# Motherboard_simple.net
KiCad netlist of a schematic drawn in EAGLE
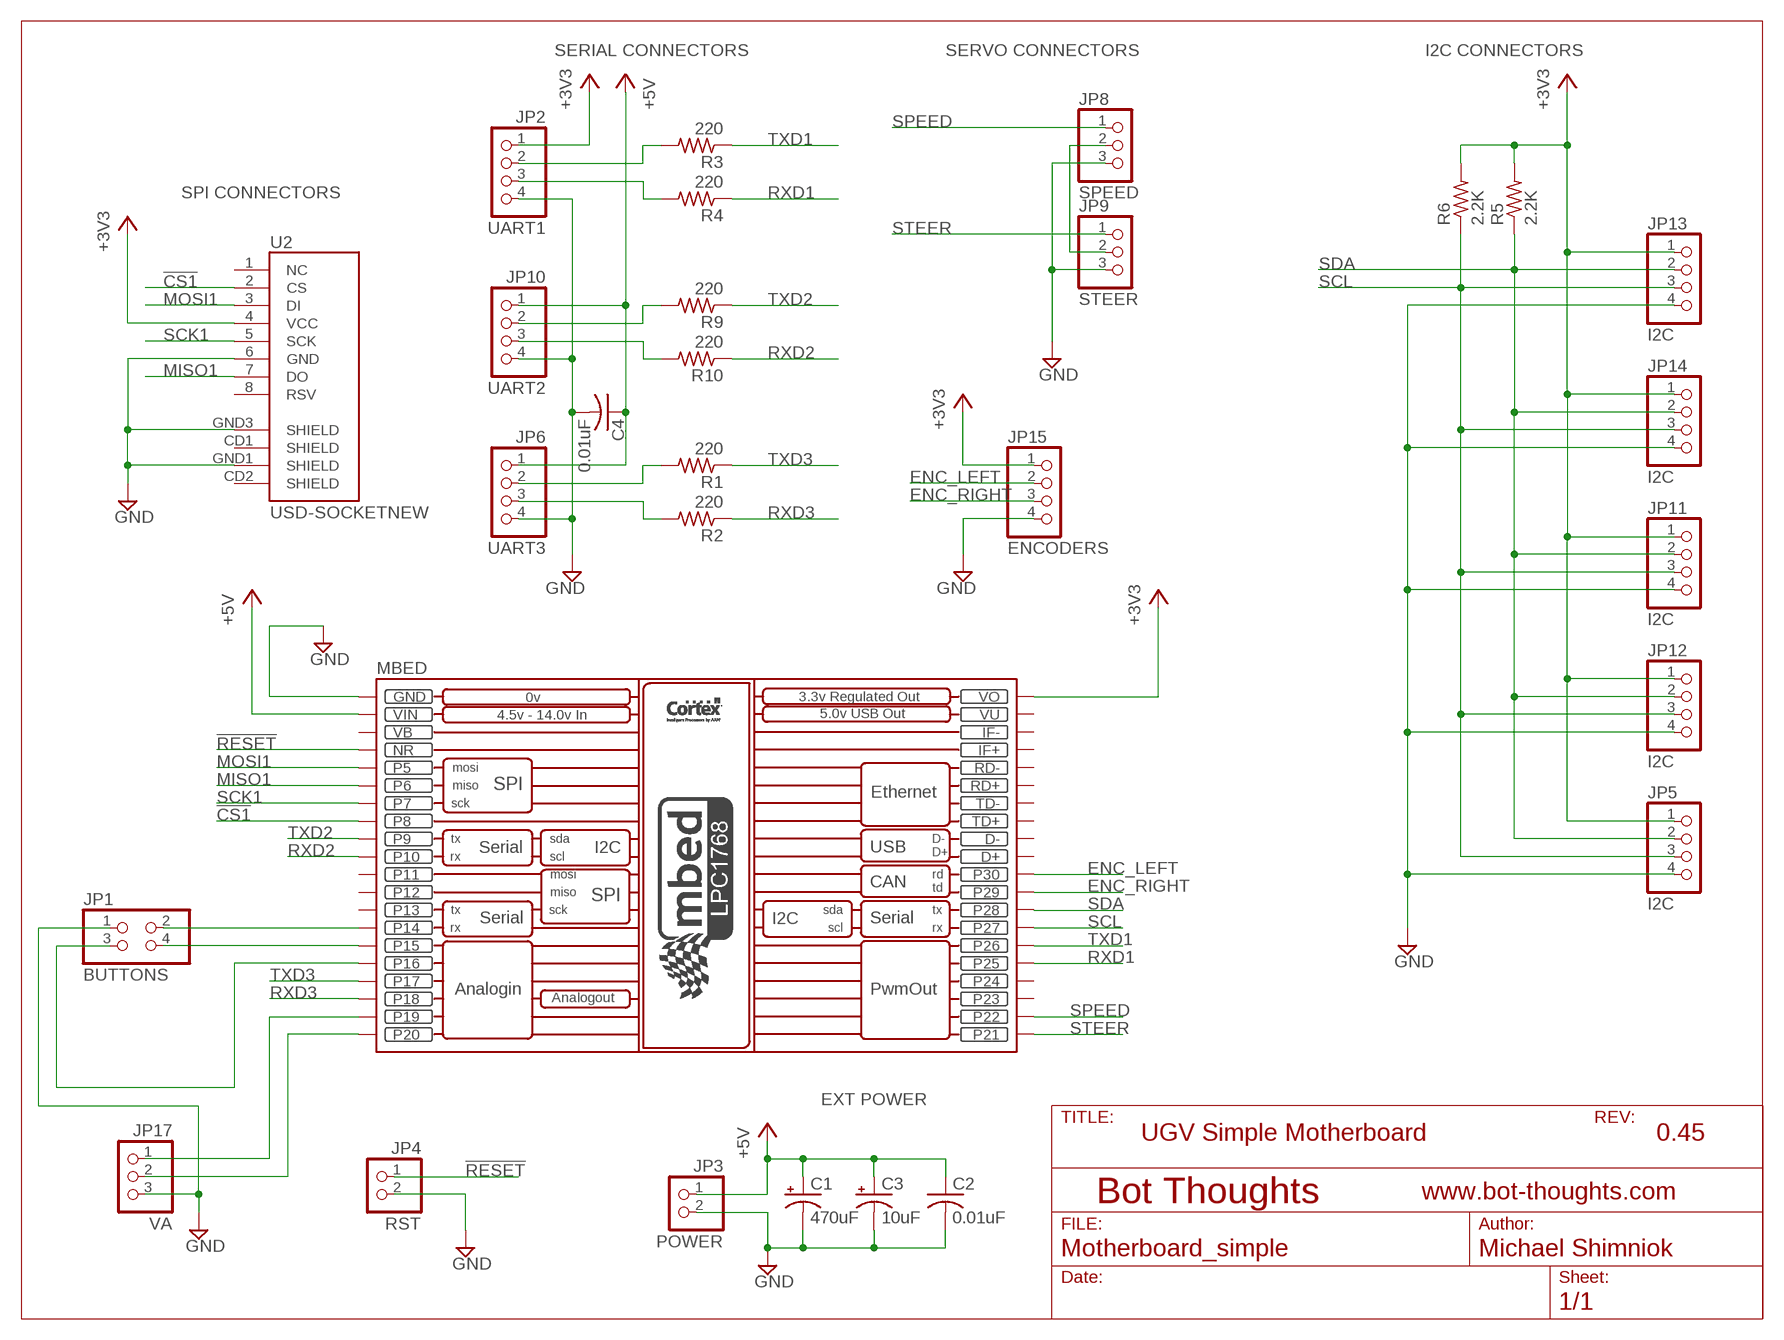
[diagram p0: schematic, sheet 1]

(export (version "E")
  (design (tool "Eeschema 10.0.6"))
  (components
    (comp (ref "C1")
      (value "470uF")
      (footprint "eagle-import:E2,5-6")
      (libsource (lib "eagle-import") (part "CPOL-USE2.5-6"))
    )
    (comp (ref "C2")
      (value "0.01uF")
      (footprint "eagle-import:C050-025X075")
      (libsource (lib "eagle-import") (part "C-US050-025X075"))
    )
    (comp (ref "C3")
      (value "10uF")
      (footprint "eagle-import:E2,5-6")
      (libsource (lib "eagle-import") (part "CPOL-USE2.5-6"))
    )
    (comp (ref "C4")
      (value "0.01uF")
      (footprint "eagle-import:C050-025X075")
      (libsource (lib "eagle-import") (part "C-US050-025X075"))
    )
    (comp (ref "JP1")
      (value "BUTTONS")
      (footprint "eagle-import:2X02")
      (libsource (lib "eagle-import") (part "PINHD-2X02_2.54"))
    )
    (comp (ref "JP2")
      (value "UART1")
      (footprint "eagle-import:1X04-S")
      (libsource (lib "eagle-import") (part "PINHD-1X04_2.54-S"))
    )
    (comp (ref "JP3")
      (value "POWER")
      (footprint "eagle-import:1X02-S")
      (libsource (lib "eagle-import") (part "PINHD-1X02_2.54-S"))
    )
    (comp (ref "JP4")
      (value "RST")
      (footprint "eagle-import:1X02-S")
      (libsource (lib "eagle-import") (part "PINHD-1X02_2.54-S"))
    )
    (comp (ref "JP5")
      (value "I2C")
      (footprint "eagle-import:1X04-S")
      (libsource (lib "eagle-import") (part "PINHD-1X04_2.54-S"))
    )
    (comp (ref "JP6")
      (value "UART3")
      (footprint "eagle-import:1X04-S")
      (libsource (lib "eagle-import") (part "PINHD-1X04_2.54-S"))
    )
    (comp (ref "JP8")
      (value "SPEED")
      (footprint "eagle-import:1X03-S")
      (libsource (lib "eagle-import") (part "PINHD-1X03_2.54-S"))
    )
    (comp (ref "JP9")
      (value "STEER")
      (footprint "eagle-import:1X03-S")
      (libsource (lib "eagle-import") (part "PINHD-1X03_2.54-S"))
    )
    (comp (ref "JP10")
      (value "UART2")
      (footprint "eagle-import:1X04-S")
      (libsource (lib "eagle-import") (part "PINHD-1X04_2.54-S"))
    )
    (comp (ref "JP11")
      (value "I2C")
      (footprint "eagle-import:1X04-S")
      (libsource (lib "eagle-import") (part "PINHD-1X04_2.54-S"))
    )
    (comp (ref "JP12")
      (value "I2C")
      (footprint "eagle-import:1X04-S")
      (libsource (lib "eagle-import") (part "PINHD-1X04_2.54-S"))
    )
    (comp (ref "JP13")
      (value "I2C")
      (footprint "eagle-import:1X04-S")
      (libsource (lib "eagle-import") (part "PINHD-1X04_2.54-S"))
    )
    (comp (ref "JP14")
      (value "I2C")
      (footprint "eagle-import:1X04-S")
      (libsource (lib "eagle-import") (part "PINHD-1X04_2.54-S"))
    )
    (comp (ref "JP15")
      (value "ENCODERS")
      (footprint "eagle-import:1X04-S")
      (libsource (lib "eagle-import") (part "PINHD-1X04_2.54-S"))
    )
    (comp (ref "JP17")
      (value "VA")
      (footprint "eagle-import:1X03-S")
      (libsource (lib "eagle-import") (part "PINHD-1X03_2.54-S"))
    )
    (comp (ref "MBED")
      (value "MBED_NXP_LPC1768")
      (footprint "eagle-import:MBED-KIT")
      (fields (field (name "MPN") "2212S-20SG-85"))
      (libsource (lib "eagle-import") (part "MBED_NXP_LPC1768"))
    )
    (comp (ref "R1")
      (value "220")
      (footprint "eagle-import:0204_5")
      (fields (field (name "MPN") "WCR0805-220RFI"))
      (libsource (lib "eagle-import") (part "R-US_0204/5"))
    )
    (comp (ref "R2")
      (value "220")
      (footprint "eagle-import:0204_5")
      (fields (field (name "MPN") "WCR0805-220RFI"))
      (libsource (lib "eagle-import") (part "R-US_0204/5"))
    )
    (comp (ref "R3")
      (value "220")
      (footprint "eagle-import:0204_5")
      (fields (field (name "MPN") "WCR0805-220RFI"))
      (libsource (lib "eagle-import") (part "R-US_0204/5"))
    )
    (comp (ref "R4")
      (value "220")
      (footprint "eagle-import:0204_5")
      (fields (field (name "MPN") "WCR0805-220RFI"))
      (libsource (lib "eagle-import") (part "R-US_0204/5"))
    )
    (comp (ref "R5")
      (value "2.2K")
      (footprint "eagle-import:0204_5")
      (libsource (lib "eagle-import") (part "R-US_0204/5"))
    )
    (comp (ref "R6")
      (value "2.2K")
      (footprint "eagle-import:0204_5")
      (libsource (lib "eagle-import") (part "R-US_0204/5"))
    )
    (comp (ref "R9")
      (value "220")
      (footprint "eagle-import:0204_5")
      (fields (field (name "MPN") "WCR0805-220RFI"))
      (libsource (lib "eagle-import") (part "R-US_0204/5"))
    )
    (comp (ref "R10")
      (value "220")
      (footprint "eagle-import:0204_5")
      (fields (field (name "MPN") "WCR0805-220RFI"))
      (libsource (lib "eagle-import") (part "R-US_0204/5"))
    )
    (comp (ref "U2")
      (value "USD-SOCKETNEW")
      (footprint "eagle-import:MICRO-SD-SOCKET-PP")
      (libsource (lib "eagle-import") (part "USD-SOCKETNEW"))
    )
  )
  (nets
    (net (code "1") (name "+3V3") (class "Default")
      (node (ref "JP11") (pin "1") (pinfunction "1_1") (pintype "passive"))
      (node (ref "JP12") (pin "1") (pinfunction "1_1") (pintype "passive"))
      (node (ref "JP13") (pin "1") (pinfunction "1_1") (pintype "passive"))
      (node (ref "JP14") (pin "1") (pinfunction "1_1") (pintype "passive"))
      (node (ref "JP15") (pin "1") (pinfunction "1_1") (pintype "passive"))
      (node (ref "JP2") (pin "1") (pinfunction "1_1") (pintype "passive"))
      (node (ref "JP5") (pin "1") (pinfunction "1_1") (pintype "passive"))
      (node (ref "MBED") (pin "VOUT") (pinfunction "VO_VOUT") (pintype "power_in"))
      (node (ref "R5") (pin "2") (pinfunction "2_2") (pintype "passive"))
      (node (ref "R6") (pin "2") (pinfunction "2_2") (pintype "passive"))
      (node (ref "U2") (pin "4") (pinfunction "VCC_4") (pintype "bidirectional"))
    )
    (net (code "2") (name "+5V") (class "Default")
      (node (ref "C1") (pin "+") (pinfunction "+_+") (pintype "passive"))
      (node (ref "C2") (pin "1") (pinfunction "1_1") (pintype "passive"))
      (node (ref "C3") (pin "+") (pinfunction "+_+") (pintype "passive"))
      (node (ref "C4") (pin "1") (pinfunction "1_1") (pintype "passive"))
      (node (ref "JP10") (pin "1") (pinfunction "1_1") (pintype "passive"))
      (node (ref "JP3") (pin "1") (pinfunction "1_1") (pintype "passive"))
      (node (ref "JP6") (pin "1") (pinfunction "1_1") (pintype "passive"))
      (node (ref "MBED") (pin "VIN") (pinfunction "VIN_VIN") (pintype "power_in"))
    )
    (net (code "3") (name "/ENC_LEFT") (class "Default")
      (node (ref "JP15") (pin "2") (pinfunction "2_2") (pintype "passive"))
      (node (ref "MBED") (pin "P$30") (pinfunction "P30_P$30") (pintype "bidirectional"))
    )
    (net (code "4") (name "/ENC_RIGHT") (class "Default")
      (node (ref "JP15") (pin "3") (pinfunction "3_3") (pintype "passive"))
      (node (ref "MBED") (pin "P$29") (pinfunction "P29_P$29") (pintype "bidirectional"))
    )
    (net (code "5") (name "/MISO1") (class "Default")
      (node (ref "MBED") (pin "P$6") (pinfunction "P6_P$6") (pintype "bidirectional"))
      (node (ref "U2") (pin "7") (pinfunction "DO_7") (pintype "bidirectional"))
    )
    (net (code "6") (name "/MOSI1") (class "Default")
      (node (ref "MBED") (pin "P$5") (pinfunction "P5_P$5") (pintype "bidirectional"))
      (node (ref "U2") (pin "3") (pinfunction "DI_3") (pintype "bidirectional"))
    )
    (net (code "7") (name "/RXD1") (class "Default")
      (node (ref "MBED") (pin "P$25") (pinfunction "P25_P$25") (pintype "bidirectional"))
      (node (ref "R4") (pin "1") (pinfunction "1_1") (pintype "passive"))
    )
    (net (code "8") (name "/RXD2") (class "Default")
      (node (ref "MBED") (pin "P$10") (pinfunction "P10_P$10") (pintype "bidirectional"))
      (node (ref "R10") (pin "1") (pinfunction "1_1") (pintype "passive"))
    )
    (net (code "9") (name "/RXD3") (class "Default")
      (node (ref "MBED") (pin "P$18") (pinfunction "P18_P$18") (pintype "bidirectional"))
      (node (ref "R2") (pin "1") (pinfunction "1_1") (pintype "passive"))
    )
    (net (code "10") (name "/SCK1") (class "Default")
      (node (ref "MBED") (pin "P$7") (pinfunction "P7_P$7") (pintype "bidirectional"))
      (node (ref "U2") (pin "5") (pinfunction "SCK_5") (pintype "bidirectional"))
    )
    (net (code "11") (name "/SCL") (class "Default")
      (node (ref "JP11") (pin "3") (pinfunction "3_3") (pintype "passive"))
      (node (ref "JP12") (pin "3") (pinfunction "3_3") (pintype "passive"))
      (node (ref "JP13") (pin "3") (pinfunction "3_3") (pintype "passive"))
      (node (ref "JP14") (pin "3") (pinfunction "3_3") (pintype "passive"))
      (node (ref "JP5") (pin "3") (pinfunction "3_3") (pintype "passive"))
      (node (ref "MBED") (pin "P$27") (pinfunction "P27_P$27") (pintype "bidirectional"))
      (node (ref "R6") (pin "1") (pinfunction "1_1") (pintype "passive"))
    )
    (net (code "12") (name "/SDA") (class "Default")
      (node (ref "JP11") (pin "2") (pinfunction "2_2") (pintype "passive"))
      (node (ref "JP12") (pin "2") (pinfunction "2_2") (pintype "passive"))
      (node (ref "JP13") (pin "2") (pinfunction "2_2") (pintype "passive"))
      (node (ref "JP14") (pin "2") (pinfunction "2_2") (pintype "passive"))
      (node (ref "JP5") (pin "2") (pinfunction "2_2") (pintype "passive"))
      (node (ref "MBED") (pin "P$28") (pinfunction "P28_P$28") (pintype "bidirectional"))
      (node (ref "R5") (pin "1") (pinfunction "1_1") (pintype "passive"))
    )
    (net (code "13") (name "/SPEED") (class "Default")
      (node (ref "JP8") (pin "1") (pinfunction "1_1") (pintype "passive"))
      (node (ref "MBED") (pin "P$22") (pinfunction "P22_P$22") (pintype "bidirectional"))
    )
    (net (code "14") (name "/STEER") (class "Default")
      (node (ref "JP9") (pin "1") (pinfunction "1_1") (pintype "passive"))
      (node (ref "MBED") (pin "P$21") (pinfunction "P21_P$21") (pintype "bidirectional"))
    )
    (net (code "15") (name "/TXD1") (class "Default")
      (node (ref "MBED") (pin "P$26") (pinfunction "P26_P$26") (pintype "bidirectional"))
      (node (ref "R3") (pin "1") (pinfunction "1_1") (pintype "passive"))
    )
    (net (code "16") (name "/TXD2") (class "Default")
      (node (ref "MBED") (pin "P$9") (pinfunction "P9_P$9") (pintype "bidirectional"))
      (node (ref "R9") (pin "1") (pinfunction "1_1") (pintype "passive"))
    )
    (net (code "17") (name "/TXD3") (class "Default")
      (node (ref "MBED") (pin "P$17") (pinfunction "P17_P$17") (pintype "bidirectional"))
      (node (ref "R1") (pin "1") (pinfunction "1_1") (pintype "passive"))
    )
    (net (code "18") (name "/VB") (class "Default")
      (node (ref "MBED") (pin "VB") (pinfunction "VB_VB") (pintype "power_in"))
    )
    (net (code "19") (name "/VU") (class "Default")
      (node (ref "MBED") (pin "VU") (pinfunction "VU_VU") (pintype "power_in"))
    )
    (net (code "20") (name "/~{CS1}") (class "Default")
      (node (ref "MBED") (pin "P$8") (pinfunction "P8_P$8") (pintype "bidirectional"))
      (node (ref "U2") (pin "2") (pinfunction "CS_2") (pintype "bidirectional"))
    )
    (net (code "21") (name "/~{RESET}") (class "Default")
      (node (ref "JP4") (pin "1") (pinfunction "1_1") (pintype "passive"))
      (node (ref "MBED") (pin "NR") (pinfunction "NR_NR") (pintype "power_in"))
    )
    (net (code "22") (name "GND") (class "Default")
      (node (ref "C1") (pin "-") (pinfunction "-_-") (pintype "passive"))
      (node (ref "C2") (pin "2") (pinfunction "2_2") (pintype "passive"))
      (node (ref "C3") (pin "-") (pinfunction "-_-") (pintype "passive"))
      (node (ref "C4") (pin "2") (pinfunction "2_2") (pintype "passive"))
      (node (ref "JP1") (pin "1") (pinfunction "1_1") (pintype "passive"))
      (node (ref "JP10") (pin "4") (pinfunction "4_4") (pintype "passive"))
      (node (ref "JP11") (pin "4") (pinfunction "4_4") (pintype "passive"))
      (node (ref "JP12") (pin "4") (pinfunction "4_4") (pintype "passive"))
      (node (ref "JP13") (pin "4") (pinfunction "4_4") (pintype "passive"))
      (node (ref "JP14") (pin "4") (pinfunction "4_4") (pintype "passive"))
      (node (ref "JP15") (pin "4") (pinfunction "4_4") (pintype "passive"))
      (node (ref "JP17") (pin "3") (pinfunction "3_3") (pintype "passive"))
      (node (ref "JP2") (pin "4") (pinfunction "4_4") (pintype "passive"))
      (node (ref "JP3") (pin "2") (pinfunction "2_2") (pintype "passive"))
      (node (ref "JP4") (pin "2") (pinfunction "2_2") (pintype "passive"))
      (node (ref "JP5") (pin "4") (pinfunction "4_4") (pintype "passive"))
      (node (ref "JP6") (pin "4") (pinfunction "4_4") (pintype "passive"))
      (node (ref "JP8") (pin "3") (pinfunction "3_3") (pintype "passive"))
      (node (ref "JP9") (pin "3") (pinfunction "3_3") (pintype "passive"))
      (node (ref "MBED") (pin "GND") (pinfunction "GND_GND") (pintype "power_in"))
      (node (ref "U2") (pin "6") (pinfunction "GND_6") (pintype "bidirectional"))
      (node (ref "U2") (pin "GND1") (pinfunction "SHIELD_GND1") (pintype "bidirectional"))
      (node (ref "U2") (pin "GND3") (pinfunction "SHIELD_GND3") (pintype "bidirectional"))
    )
    (net (code "23") (name "Net-(JP2-Pad2)") (class "Default")
      (node (ref "JP2") (pin "2") (pinfunction "2_2") (pintype "passive"))
      (node (ref "R3") (pin "2") (pinfunction "2_2") (pintype "passive"))
    )
    (net (code "24") (name "Net-(JP2-Pad3)") (class "Default")
      (node (ref "JP2") (pin "3") (pinfunction "3_3") (pintype "passive"))
      (node (ref "R4") (pin "2") (pinfunction "2_2") (pintype "passive"))
    )
    (net (code "25") (name "Net-(JP6-Pad2)") (class "Default")
      (node (ref "JP6") (pin "2") (pinfunction "2_2") (pintype "passive"))
      (node (ref "R1") (pin "2") (pinfunction "2_2") (pintype "passive"))
    )
    (net (code "26") (name "Net-(JP6-Pad3)") (class "Default")
      (node (ref "JP6") (pin "3") (pinfunction "3_3") (pintype "passive"))
      (node (ref "R2") (pin "2") (pinfunction "2_2") (pintype "passive"))
    )
    (net (code "27") (name "Net-(JP8-Pad2)") (class "Default")
      (node (ref "JP8") (pin "2") (pinfunction "2_2") (pintype "passive"))
      (node (ref "JP9") (pin "2") (pinfunction "2_2") (pintype "passive"))
    )
    (net (code "28") (name "Net-(JP10-Pad2)") (class "Default")
      (node (ref "JP10") (pin "2") (pinfunction "2_2") (pintype "passive"))
      (node (ref "R9") (pin "2") (pinfunction "2_2") (pintype "passive"))
    )
    (net (code "29") (name "Net-(JP10-Pad3)") (class "Default")
      (node (ref "JP10") (pin "3") (pinfunction "3_3") (pintype "passive"))
      (node (ref "R10") (pin "2") (pinfunction "2_2") (pintype "passive"))
    )
    (net (code "30") (name "Net-(MBED-P14)") (class "Default")
      (node (ref "JP1") (pin "2") (pinfunction "2_2") (pintype "passive"))
      (node (ref "MBED") (pin "P$14") (pinfunction "P14_P$14") (pintype "bidirectional"))
    )
    (net (code "31") (name "Net-(MBED-P15)") (class "Default")
      (node (ref "JP1") (pin "4") (pinfunction "4_4") (pintype "passive"))
      (node (ref "MBED") (pin "P$15") (pinfunction "P15_P$15") (pintype "bidirectional"))
    )
    (net (code "32") (name "Net-(MBED-P16)") (class "Default")
      (node (ref "JP1") (pin "3") (pinfunction "3_3") (pintype "passive"))
      (node (ref "MBED") (pin "P$16") (pinfunction "P16_P$16") (pintype "bidirectional"))
    )
    (net (code "33") (name "Net-(MBED-P19)") (class "Default")
      (node (ref "JP17") (pin "1") (pinfunction "1_1") (pintype "passive"))
      (node (ref "MBED") (pin "P$19") (pinfunction "P19_P$19") (pintype "bidirectional"))
    )
    (net (code "34") (name "Net-(MBED-P20)") (class "Default")
      (node (ref "JP17") (pin "2") (pinfunction "2_2") (pintype "passive"))
      (node (ref "MBED") (pin "P$20") (pinfunction "P20_P$20") (pintype "bidirectional"))
    )
    (net (code "35") (name "unconnected-(MBED-P11-PadP$11)") (class "Default")
      (node (ref "MBED") (pin "P$11") (pinfunction "P11_P$11") (pintype "bidirectional"))
    )
    (net (code "36") (name "unconnected-(MBED-P12-PadP$12)") (class "Default")
      (node (ref "MBED") (pin "P$12") (pinfunction "P12_P$12") (pintype "bidirectional"))
    )
    (net (code "37") (name "unconnected-(MBED-P13-PadP$13)") (class "Default")
      (node (ref "MBED") (pin "P$13") (pinfunction "P13_P$13") (pintype "bidirectional"))
    )
    (net (code "38") (name "unconnected-(MBED-P23-PadP$23)") (class "Default")
      (node (ref "MBED") (pin "P$23") (pinfunction "P23_P$23") (pintype "bidirectional"))
    )
    (net (code "39") (name "unconnected-(MBED-P24-PadP$24)") (class "Default")
      (node (ref "MBED") (pin "P$24") (pinfunction "P24_P$24") (pintype "bidirectional"))
    )
    (net (code "40") (name "unconnected-(MBED-PadD+)") (class "Default")
      (node (ref "MBED") (pin "D+") (pinfunction "D+_D+") (pintype "bidirectional"))
    )
    (net (code "41") (name "unconnected-(MBED-PadD-)") (class "Default")
      (node (ref "MBED") (pin "D-") (pinfunction "D-_D-") (pintype "bidirectional"))
    )
    (net (code "42") (name "unconnected-(MBED-PadIF+)") (class "Default")
      (node (ref "MBED") (pin "IF+") (pinfunction "IF+_IF+") (pintype "bidirectional"))
    )
    (net (code "43") (name "unconnected-(MBED-PadIF-)") (class "Default")
      (node (ref "MBED") (pin "IF-") (pinfunction "IF-_IF-") (pintype "bidirectional"))
    )
    (net (code "44") (name "unconnected-(MBED-PadRD+)") (class "Default")
      (node (ref "MBED") (pin "RD+") (pinfunction "RD+_RD+") (pintype "bidirectional"))
    )
    (net (code "45") (name "unconnected-(MBED-PadRD-)") (class "Default")
      (node (ref "MBED") (pin "RD-") (pinfunction "RD-_RD-") (pintype "bidirectional"))
    )
    (net (code "46") (name "unconnected-(MBED-PadTD+)") (class "Default")
      (node (ref "MBED") (pin "TD+") (pinfunction "TD+_TD+") (pintype "bidirectional"))
    )
    (net (code "47") (name "unconnected-(MBED-PadTD-)") (class "Default")
      (node (ref "MBED") (pin "TD-") (pinfunction "TD-_TD-") (pintype "bidirectional"))
    )
    (net (code "48") (name "unconnected-(U2-NC-Pad1)") (class "Default")
      (node (ref "U2") (pin "1") (pinfunction "NC_1") (pintype "bidirectional"))
    )
    (net (code "49") (name "unconnected-(U2-RSV-Pad8)") (class "Default")
      (node (ref "U2") (pin "8") (pinfunction "RSV_8") (pintype "bidirectional"))
    )
    (net (code "50") (name "unconnected-(U2-SHIELD-PadCD1)") (class "Default")
      (node (ref "U2") (pin "CD1") (pinfunction "SHIELD_CD1") (pintype "bidirectional"))
    )
    (net (code "51") (name "unconnected-(U2-SHIELD-PadCD2)") (class "Default")
      (node (ref "U2") (pin "CD2") (pinfunction "SHIELD_CD2") (pintype "bidirectional"))
    )
  )
)
